# mcu_power_supply.net
KiCad netlist of a schematic drawn in Altium Designer
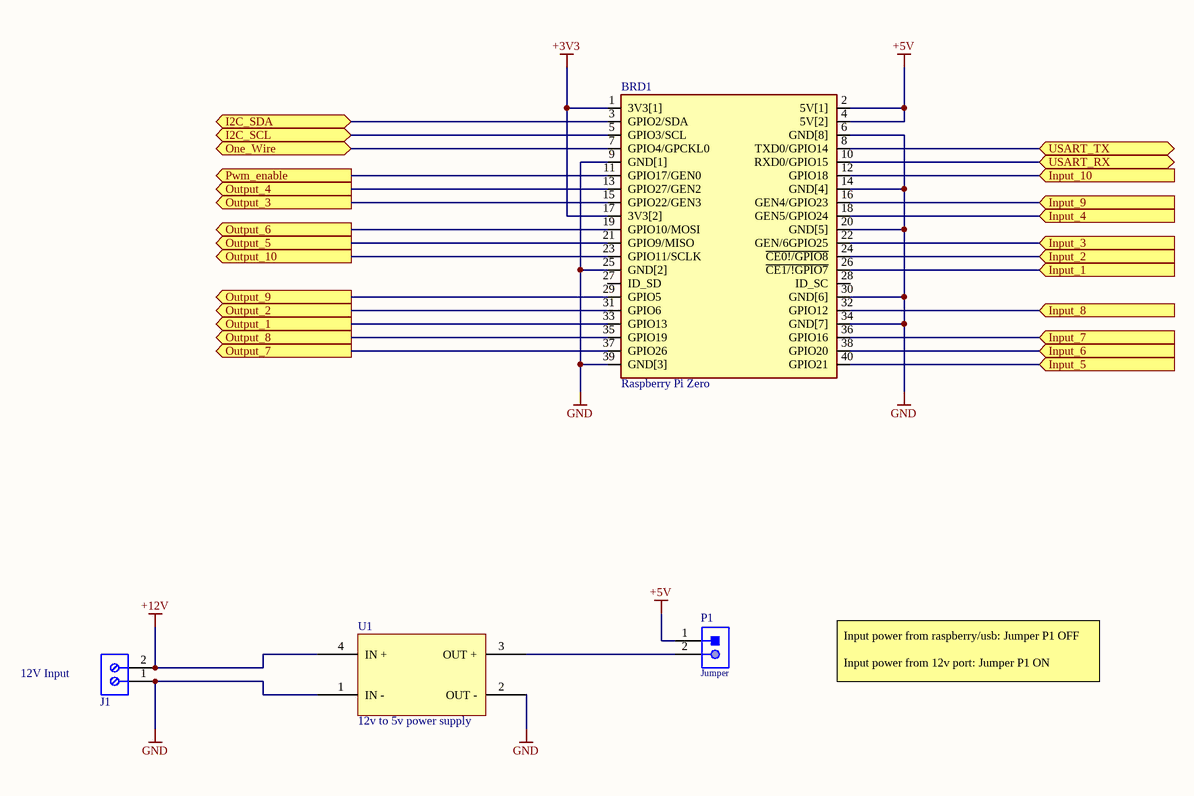
[diagram p0: mcu_power_supply.SchDoc]

(export (version "E")
  (design (tool "Eeschema 10.0.6"))
  (components
    (comp (ref "BRD1")
      (value "Raspberry Pi Zero")
      (footprint "RASPBERRY_PI_ZERO")
      (description "Raspberry Pi Zero with Header")
      (fields (field (name "MP") "ADA3708") (field (name "MF") "Raspberry Pi"))
      (libsource (lib "integrated_library") (part "MCU_raspberryPi_zero"))
    )
    (comp (ref "J1")
      (value "282836-2")
      (footprint "TECO-282836-2_V")
      (description "Female Header, Pitch 5 mm, 1 x 2 Position, Height 10 mm, Tail Length 3.5 mm, Rohs, Bulk")
      (fields (field (name "VOLTAGE") "300V") (field (name "MANUFACTURER") "TE Connectivity"))
      (libsource (lib "Altium Content Vault") (part "CN-1P-F-TB2"))
    )
    (comp (ref "P1")
      (value "Jumper")
      (footprint "61300211121")
      (description "THT Vertical Pin Header WR-PHD, Pitch 2.54 mm, Single Row, 2 pins")
      (fields
        (field (name "MANUFACTURER") "Wurth Elektronik")
        (field (name "PART NUMBER") "61300211121")
        (field (name "PUBLISHER") "WurthElektronik")
      )
      (libsource (lib "Altium Content Vault") (part "WE-CN-1P-M-R2"))
    )
    (comp (ref "U1")
      (value "12v to 5v power supply")
      (footprint "5v_power_supply")
      (description "12V TO 5V buck converter")
      (libsource (lib "Schlib") (part "power_supply_5v"))
    )
  )
  (nets
    (net (code "1") (name "+3V3") (class "Default")
      (node (ref "BRD1") (pin "1") (pinfunction "3V3[1]_1") (pintype "power_in"))
      (node (ref "BRD1") (pin "17") (pinfunction "3V3[2]_17") (pintype "power_in"))
    )
    (net (code "2") (name "+5V") (class "Default")
      (node (ref "BRD1") (pin "2") (pinfunction "5V[1]_2") (pintype "power_in"))
      (node (ref "BRD1") (pin "4") (pinfunction "5V[2]_4") (pintype "power_in"))
      (node (ref "P1") (pin "1") (pinfunction "1_1") (pintype "passive"))
    )
    (net (code "3") (name "+12V") (class "Default")
      (node (ref "J1") (pin "2") (pinfunction "2_2") (pintype "passive"))
      (node (ref "U1") (pin "4") (pinfunction "IN_+_4") (pintype "passive"))
    )
    (net (code "4") (name "/I2C_SCL") (class "Default")
      (node (ref "BRD1") (pin "5") (pinfunction "GPIO3/SCL_5") (pintype "bidirectional"))
    )
    (net (code "5") (name "/I2C_SDA") (class "Default")
      (node (ref "BRD1") (pin "3") (pinfunction "GPIO2/SDA_3") (pintype "bidirectional"))
    )
    (net (code "6") (name "/Input_1") (class "Default")
      (node (ref "BRD1") (pin "26") (pinfunction "~{CE1/!GPIO7}_26") (pintype "bidirectional"))
    )
    (net (code "7") (name "/Input_2") (class "Default")
      (node (ref "BRD1") (pin "24") (pinfunction "~{CE0!/GPIO8}_24") (pintype "bidirectional"))
    )
    (net (code "8") (name "/Input_3") (class "Default")
      (node (ref "BRD1") (pin "22") (pinfunction "GEN/6GPIO25_22") (pintype "bidirectional"))
    )
    (net (code "9") (name "/Input_4") (class "Default")
      (node (ref "BRD1") (pin "18") (pinfunction "GEN5/GPIO24_18") (pintype "bidirectional"))
    )
    (net (code "10") (name "/Input_5") (class "Default")
      (node (ref "BRD1") (pin "40") (pinfunction "GPIO21_40") (pintype "bidirectional"))
    )
    (net (code "11") (name "/Input_6") (class "Default")
      (node (ref "BRD1") (pin "38") (pinfunction "GPIO20_38") (pintype "bidirectional"))
    )
    (net (code "12") (name "/Input_7") (class "Default")
      (node (ref "BRD1") (pin "36") (pinfunction "GPIO16_36") (pintype "bidirectional"))
    )
    (net (code "13") (name "/Input_8") (class "Default")
      (node (ref "BRD1") (pin "32") (pinfunction "GPIO12_32") (pintype "bidirectional"))
    )
    (net (code "14") (name "/Input_9") (class "Default")
      (node (ref "BRD1") (pin "16") (pinfunction "GEN4/GPIO23_16") (pintype "bidirectional"))
    )
    (net (code "15") (name "/Input_10") (class "Default")
      (node (ref "BRD1") (pin "12") (pinfunction "GPIO18_12") (pintype "bidirectional"))
    )
    (net (code "16") (name "/One_Wire") (class "Default")
      (node (ref "BRD1") (pin "7") (pinfunction "GPIO4/GPCKL0_7") (pintype "bidirectional"))
    )
    (net (code "17") (name "/Output_1") (class "Default")
      (node (ref "BRD1") (pin "33") (pinfunction "GPIO13_33") (pintype "bidirectional"))
    )
    (net (code "18") (name "/Output_2") (class "Default")
      (node (ref "BRD1") (pin "31") (pinfunction "GPIO6_31") (pintype "bidirectional"))
    )
    (net (code "19") (name "/Output_3") (class "Default")
      (node (ref "BRD1") (pin "15") (pinfunction "GPIO22/GEN3_15") (pintype "bidirectional"))
    )
    (net (code "20") (name "/Output_4") (class "Default")
      (node (ref "BRD1") (pin "13") (pinfunction "GPIO27/GEN2_13") (pintype "bidirectional"))
    )
    (net (code "21") (name "/Output_5") (class "Default")
      (node (ref "BRD1") (pin "21") (pinfunction "GPIO9/MISO_21") (pintype "bidirectional"))
    )
    (net (code "22") (name "/Output_6") (class "Default")
      (node (ref "BRD1") (pin "19") (pinfunction "GPIO10/MOSI_19") (pintype "bidirectional"))
    )
    (net (code "23") (name "/Output_7") (class "Default")
      (node (ref "BRD1") (pin "37") (pinfunction "GPIO26_37") (pintype "bidirectional"))
    )
    (net (code "24") (name "/Output_8") (class "Default")
      (node (ref "BRD1") (pin "35") (pinfunction "GPIO19_35") (pintype "bidirectional"))
    )
    (net (code "25") (name "/Output_9") (class "Default")
      (node (ref "BRD1") (pin "29") (pinfunction "GPIO5_29") (pintype "bidirectional"))
    )
    (net (code "26") (name "/Output_10") (class "Default")
      (node (ref "BRD1") (pin "23") (pinfunction "GPIO11/SCLK_23") (pintype "bidirectional"))
    )
    (net (code "27") (name "/Pwm_enable") (class "Default")
      (node (ref "BRD1") (pin "11") (pinfunction "GPIO17/GEN0_11") (pintype "bidirectional"))
    )
    (net (code "28") (name "/USART_RX") (class "Default")
      (node (ref "BRD1") (pin "10") (pinfunction "RXD0/GPIO15_10") (pintype "bidirectional"))
    )
    (net (code "29") (name "/USART_TX") (class "Default")
      (node (ref "BRD1") (pin "8") (pinfunction "TXD0/GPIO14_8") (pintype "bidirectional"))
    )
    (net (code "30") (name "GND") (class "Default")
      (node (ref "BRD1") (pin "14") (pinfunction "GND[4]_14") (pintype "power_in"))
      (node (ref "BRD1") (pin "20") (pinfunction "GND[5]_20") (pintype "power_in"))
      (node (ref "BRD1") (pin "25") (pinfunction "GND[2]_25") (pintype "power_in"))
      (node (ref "BRD1") (pin "30") (pinfunction "GND[6]_30") (pintype "power_in"))
      (node (ref "BRD1") (pin "34") (pinfunction "GND[7]_34") (pintype "power_in"))
      (node (ref "BRD1") (pin "39") (pinfunction "GND[3]_39") (pintype "power_in"))
      (node (ref "BRD1") (pin "6") (pinfunction "GND[8]_6") (pintype "power_in"))
      (node (ref "BRD1") (pin "9") (pinfunction "GND[1]_9") (pintype "power_in"))
      (node (ref "J1") (pin "1") (pinfunction "1_1") (pintype "passive"))
      (node (ref "U1") (pin "1") (pinfunction "IN_-_1") (pintype "passive"))
      (node (ref "U1") (pin "2") (pinfunction "OUT_-_2") (pintype "passive"))
    )
    (net (code "31") (name "Net-(U1-OUT_+)") (class "Default")
      (node (ref "P1") (pin "2") (pinfunction "2_2") (pintype "passive"))
      (node (ref "U1") (pin "3") (pinfunction "OUT_+_3") (pintype "passive"))
    )
    (net (code "32") (name "unconnected-(BRD1-ID_SC-Pad28)") (class "Default")
      (node (ref "BRD1") (pin "28") (pinfunction "ID_SC_28") (pintype "bidirectional"))
    )
    (net (code "33") (name "unconnected-(BRD1-ID_SD-Pad27)") (class "Default")
      (node (ref "BRD1") (pin "27") (pinfunction "ID_SD_27") (pintype "bidirectional"))
    )
  )
)
